# Sheet1.net
KiCad netlist of a schematic drawn in Altium Designer
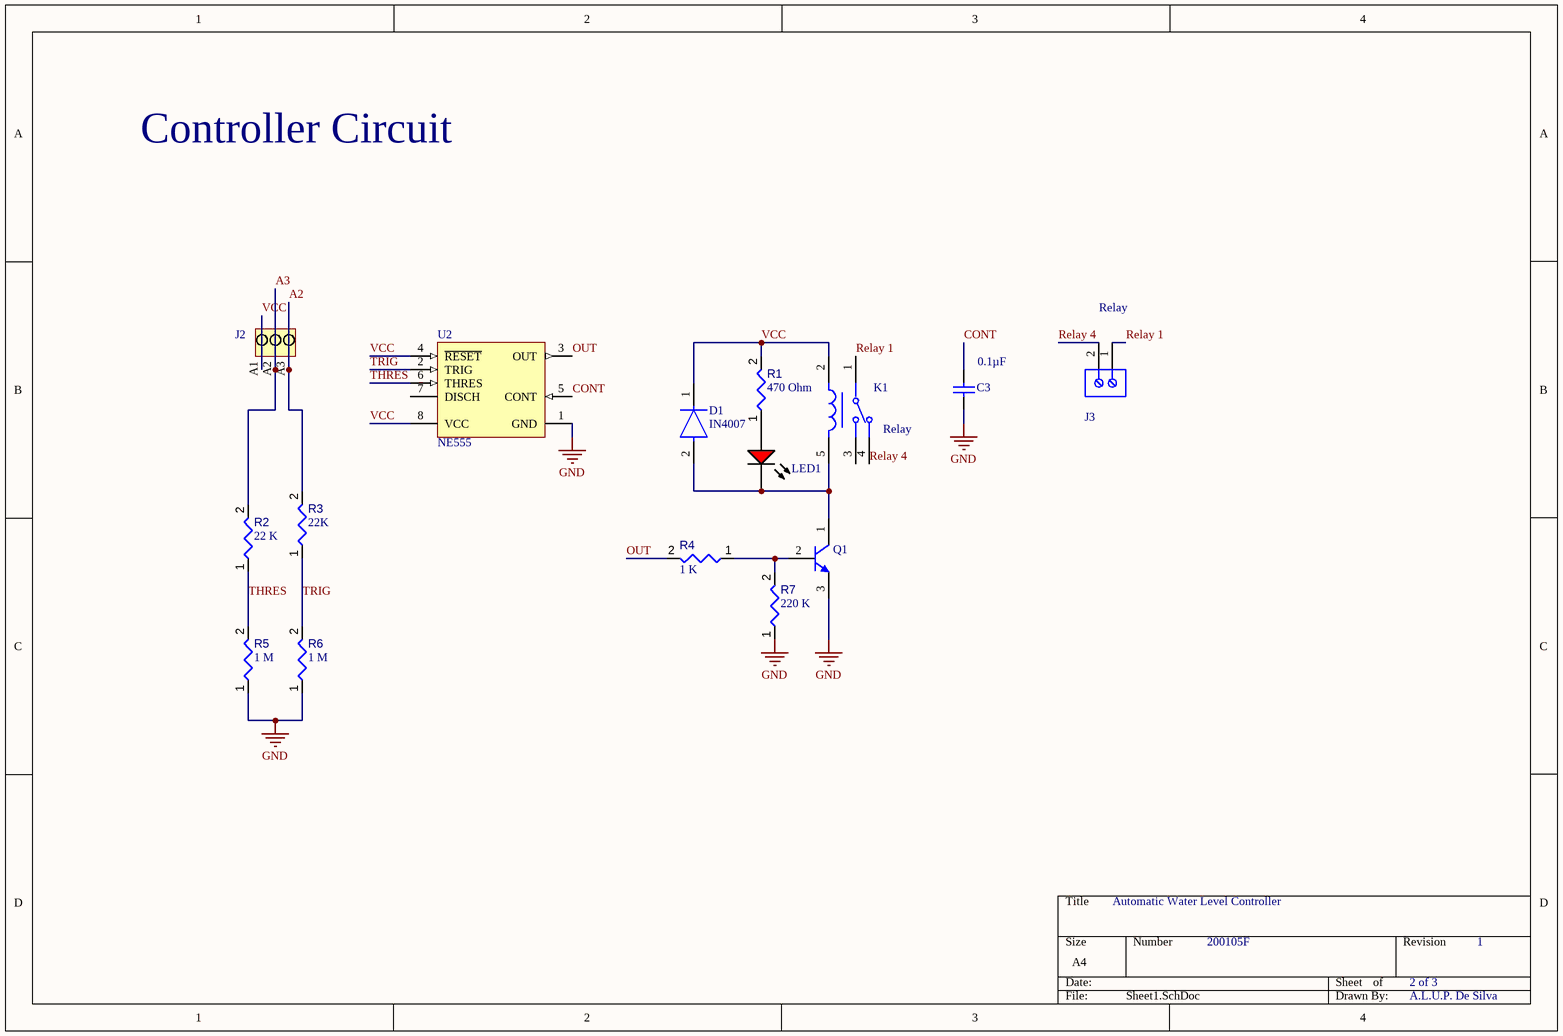
[diagram p0: Sheet1.SchDoc]

(export (version "E")
  (design (tool "Eeschema 10.0.6"))
  (components
    (comp (ref "C3")
      (value "K104K15X7RF5TL2")
      (footprint "VISH-K104K15X7RF5TL2")
      (description "Ceramic Capacitor, 100 nF, +/- 10%, 50 V, -55 to 125 degC, 2-Pin THD, RoHS, Tape and Reel")
      (fields
        (field (name "MANUFACTURER") "Vishay")
        (field (name "TOLERANCE") "±10%")
        (field (name "CAPACITANCE") "0.1µF")
      )
      (libsource (lib "Altium Content Vault") (part "CAP-NP-2"))
    )
    (comp (ref "D1")
      (value "IN4007")
      (footprint "FP-1N4007-MFG")
      (description "DIODE GEN PURP 1KV 1A DO204AL")
      (fields
        (field (name "OCTOPART") "https://octopart.com/1n4007-e3%2F54-vishay-39548207")
        (field (name "MANUFACTURER") "Vishay")
      )
      (libsource (lib "Altium Content Vault") (part "d7152d700b627762746794eb795d46e"))
    )
    (comp (ref "J2")
      (value "1715320000")
      (footprint "LM_5_00_90_03")
      (description "OMNIMATE Signal - series LM")
      (fields (field (name "MANUFACTURER") "Weidmueller"))
      (libsource (lib "Altium Content Vault") (part "Terminal_03_1x03"))
    )
    (comp (ref "J3")
      (value "Relay")
      (footprint "691102710002")
      (description "Series 102 - 5.00 mm Horizontal Entry Modular with Pressure Clamp WR-TBL, 2 pin")
      (fields
        (field (name "MANUFACTURER") "Wurth Elektronik")
        (field (name "PART NUMBER") "691102710002")
        (field (name "PUBLISHER") "WurthElektronik")
      )
      (libsource (lib "Altium Content Vault") (part "WE-CN-1P-F-TB2"))
    )
    (comp (ref "K1")
      (value "Relay")
      (footprint "FP-G5LE-14-DC5-MFG")
      (description "RELAY GEN PURPOSE SPDT 10A 5V")
      (fields
        (field (name "OCTOPART") "https://octopart.com/g5le-14-dc5-omron-28829")
        (field (name "MANUFACTURER") "Omron")
      )
      (libsource (lib "Altium Content Vault") (part "c03b8d08e5d02e70a6880f365e34168"))
    )
    (comp (ref "LED1")
      (value "HLMP-3301")
      (footprint "AVAG-HLMP-3301-2")
      (description "T-1 3/4 (5 mm) Diffused LED Lamp, 1.9 V, -40 to 100 degC, 2-Pin THD, RoHS, Bulk")
      (fields (field (name "MANUFACTURER") "Avago"))
      (libsource (lib "Altium Content Vault") (part "LED-RED-K1A2-2"))
    )
    (comp (ref "Q1")
      (value "BC547BRL1G")
      (footprint "ONSC-TO-92-3-29-11_AM_BL")
      (description "Amplifier Transistor, NPN Silicon, 3-Pin TO-92, Pb-Free, Tape and Reel")
      (fields (field (name "MANUFACTURER") "On Semiconductor"))
      (libsource (lib "Altium Content Vault") (part "ONSC-NPN-C1B2E3-3"))
    )
    (comp (ref "R1")
      (value "470 Ohm")
      (footprint "RESA60-630X240")
      (description "Axial Resistor, 475 KOhm, +/- 1%, 0.25 W, -55 to 155 degC, 2-Pin THD, RoHS, Bulk")
      (fields (field (name "POWER") "250mW") (field (name "TOLERANCE") "1%"))
      (libsource (lib "Ulindu's Workspace") (part "RES-2"))
    )
    (comp (ref "R2")
      (value "22 K")
      (footprint "RESA60-630X240")
      (description "Axial Resistor, 475 KOhm, +/- 1%, 0.25 W, -55 to 155 degC, 2-Pin THD, RoHS, Bulk")
      (fields (field (name "POWER") "250mW") (field (name "TOLERANCE") "1%"))
      (libsource (lib "Ulindu's Workspace") (part "RES-2"))
    )
    (comp (ref "R3")
      (value "22K")
      (footprint "RESA60-630X240")
      (description "Axial Resistor, 475 KOhm, +/- 1%, 0.25 W, -55 to 155 degC, 2-Pin THD, RoHS, Bulk")
      (fields (field (name "POWER") "250mW") (field (name "TOLERANCE") "1%"))
      (libsource (lib "Ulindu's Workspace") (part "RES-2"))
    )
    (comp (ref "R4")
      (value "1 K")
      (footprint "RESA60-630X240")
      (description "Axial Resistor, 475 KOhm, +/- 1%, 0.25 W, -55 to 155 degC, 2-Pin THD, RoHS, Bulk")
      (fields (field (name "POWER") "250mW") (field (name "TOLERANCE") "1%"))
      (libsource (lib "Ulindu's Workspace") (part "RES-2"))
    )
    (comp (ref "R5")
      (value "1 M")
      (footprint "RESA60-630X240")
      (description "Axial Resistor, 475 KOhm, +/- 1%, 0.25 W, -55 to 155 degC, 2-Pin THD, RoHS, Bulk")
      (fields (field (name "POWER") "250mW") (field (name "TOLERANCE") "1%"))
      (libsource (lib "Ulindu's Workspace") (part "RES-2"))
    )
    (comp (ref "R6")
      (value "1 M")
      (footprint "RESA60-630X240")
      (description "Axial Resistor, 475 KOhm, +/- 1%, 0.25 W, -55 to 155 degC, 2-Pin THD, RoHS, Bulk")
      (fields (field (name "POWER") "250mW") (field (name "TOLERANCE") "1%"))
      (libsource (lib "Ulindu's Workspace") (part "RES-2"))
    )
    (comp (ref "R7")
      (value "220 K")
      (footprint "RESA60-630X240")
      (description "Axial Resistor, 475 KOhm, +/- 1%, 0.25 W, -55 to 155 degC, 2-Pin THD, RoHS, Bulk")
      (fields (field (name "POWER") "250mW") (field (name "TOLERANCE") "1%"))
      (libsource (lib "Ulindu's Workspace") (part "RES-2"))
    )
    (comp (ref "U2")
      (value "NE555")
      (footprint "P0008A")
      (description "Precision Timer, 4.5 to 16 V, 0 to 70 degC, 8-Pin DIP, Pb-Free, Tube")
      (fields (field (name "MANUFACTURER") "TexasInstruments"))
      (libsource (lib "Altium Content Vault") (part "TI-NE555-P8"))
    )
  )
  (nets
    (net (code "1") (name "/A2") (class "Default")
      (node (ref "J2") (pin "A3") (pinfunction "A3_A3") (pintype "passive"))
      (node (ref "R3") (pin "2") (pinfunction "2_2") (pintype "passive"))
    )
    (net (code "2") (name "/A3") (class "Default")
      (node (ref "J2") (pin "A2") (pinfunction "A2_A2") (pintype "passive"))
      (node (ref "R2") (pin "2") (pinfunction "2_2") (pintype "passive"))
    )
    (net (code "3") (name "/CONT") (class "Default")
      (node (ref "C3") (pin "2") (pinfunction "2_2") (pintype "passive"))
      (node (ref "U2") (pin "5") (pinfunction "CONT_5") (pintype "input"))
    )
    (net (code "4") (name "/OUT") (class "Default")
      (node (ref "R4") (pin "2") (pinfunction "2_2") (pintype "passive"))
      (node (ref "U2") (pin "3") (pinfunction "OUT_3") (pintype "output"))
    )
    (net (code "5") (name "/Relay 1") (class "Default")
      (node (ref "J3") (pin "1") (pinfunction "1_1") (pintype "passive"))
      (node (ref "K1") (pin "1") (pinfunction "1_1") (pintype "passive"))
    )
    (net (code "6") (name "/Relay 4") (class "Default")
      (node (ref "J3") (pin "2") (pinfunction "2_2") (pintype "passive"))
      (node (ref "K1") (pin "4") (pinfunction "4_4") (pintype "passive"))
    )
    (net (code "7") (name "/THRES") (class "Default")
      (node (ref "R2") (pin "1") (pinfunction "1_1") (pintype "passive"))
      (node (ref "R5") (pin "2") (pinfunction "2_2") (pintype "passive"))
      (node (ref "U2") (pin "6") (pinfunction "THRES_6") (pintype "input"))
    )
    (net (code "8") (name "/TRIG") (class "Default")
      (node (ref "R3") (pin "1") (pinfunction "1_1") (pintype "passive"))
      (node (ref "R6") (pin "2") (pinfunction "2_2") (pintype "passive"))
      (node (ref "U2") (pin "2") (pinfunction "TRIG_2") (pintype "input"))
    )
    (net (code "9") (name "/VCC") (class "Default")
      (node (ref "D1") (pin "1") (pinfunction "C_1") (pintype "passive"))
      (node (ref "J2") (pin "A1") (pinfunction "A1_A1") (pintype "passive"))
      (node (ref "K1") (pin "2") (pinfunction "2_2") (pintype "passive"))
      (node (ref "R1") (pin "2") (pinfunction "2_2") (pintype "passive"))
      (node (ref "U2") (pin "4") (pinfunction "~{RESET}_4") (pintype "input"))
      (node (ref "U2") (pin "8") (pinfunction "VCC_8") (pintype "power_in"))
    )
    (net (code "10") (name "GND") (class "Default")
      (node (ref "C3") (pin "1") (pinfunction "1_1") (pintype "passive"))
      (node (ref "Q1") (pin "3") (pinfunction "E_3") (pintype "passive"))
      (node (ref "R5") (pin "1") (pinfunction "1_1") (pintype "passive"))
      (node (ref "R6") (pin "1") (pinfunction "1_1") (pintype "passive"))
      (node (ref "R7") (pin "1") (pinfunction "1_1") (pintype "passive"))
      (node (ref "U2") (pin "1") (pinfunction "GND_1") (pintype "power_in"))
    )
    (net (code "11") (name "Net-(D1-A)") (class "Default")
      (node (ref "D1") (pin "2") (pinfunction "A_2") (pintype "passive"))
      (node (ref "K1") (pin "5") (pinfunction "5_5") (pintype "passive"))
      (node (ref "LED1") (pin "1") (pinfunction "K_1") (pintype "passive"))
      (node (ref "Q1") (pin "1") (pinfunction "C_1") (pintype "passive"))
    )
    (net (code "12") (name "Net-(LED1-A)") (class "Default")
      (node (ref "LED1") (pin "2") (pinfunction "A_2") (pintype "passive"))
      (node (ref "R1") (pin "1") (pinfunction "1_1") (pintype "passive"))
    )
    (net (code "13") (name "Net-(Q1-B)") (class "Default")
      (node (ref "Q1") (pin "2") (pinfunction "B_2") (pintype "passive"))
      (node (ref "R4") (pin "1") (pinfunction "1_1") (pintype "passive"))
      (node (ref "R7") (pin "2") (pinfunction "2_2") (pintype "passive"))
    )
    (net (code "14") (name "unconnected-(K1-Pad3)") (class "Default")
      (node (ref "K1") (pin "3") (pinfunction "3_3") (pintype "passive"))
    )
    (net (code "15") (name "unconnected-(U2-DISCH-Pad7)") (class "Default")
      (node (ref "U2") (pin "7") (pinfunction "DISCH_7") (pintype "open_collector"))
    )
  )
)
